# GPIO_AND_SERIAL.net
KiCad netlist of a schematic drawn in Altium Designer
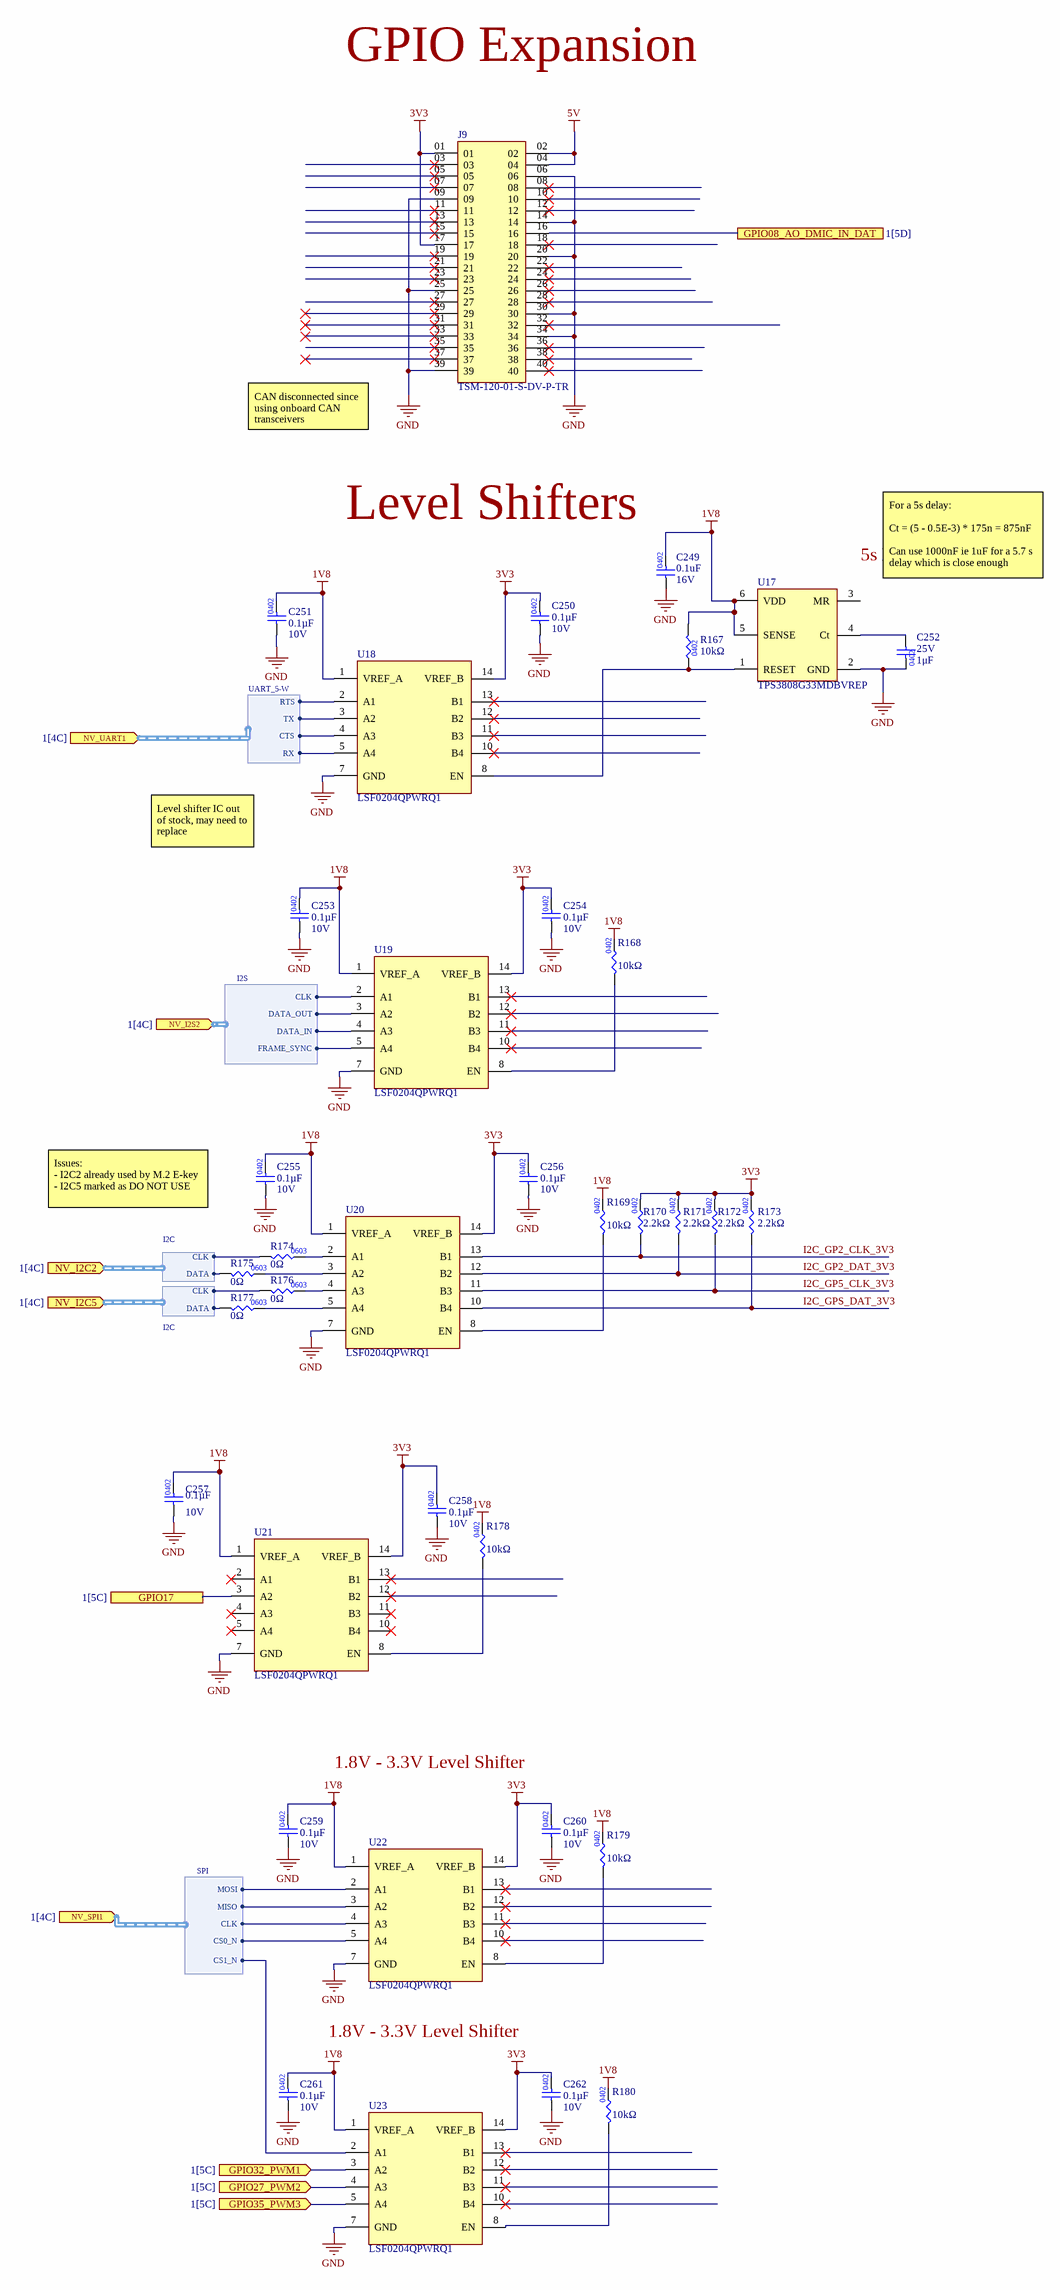
[diagram p0: GPIO AND SERIAL.SchDoc]

(export (version "E")
  (design (tool "Eeschema 10.0.6"))
  (components
    (comp (ref "C249")
      (value "CAP_0.1uF_16V_X7R_0402")
      (footprint "CAP0402")
      (description "CAP CER 0.1UF 16V X7R 0402")
      (fields (field (name "CAPACITANCE") "0.1uF") (field (name "VOLTAGE RATING") "16V"))
      (libsource (lib "UWRT_Schematic_Library_2020") (part "CAP_0.1uF_16V_X7R_0402"))
    )
    (comp (ref "C250")
      (value "0.1µF")
      (footprint "CAP0402")
      (description "CAP CER 0.1UF 10V X7R 0402")
      (fields (field (name "VOLTAGE RATING") "10V") (field (name "Comment") "CAP_0.1uF_10V_0402"))
      (libsource (lib "UWRT_Schematic_Library_2020") (part "CAP_0.1uF_10V_0402"))
    )
    (comp (ref "C251")
      (value "0.1µF")
      (footprint "CAP0402")
      (description "CAP CER 0.1UF 10V X7R 0402")
      (fields (field (name "VOLTAGE RATING") "10V") (field (name "Comment") "CAP_0.1uF_10V_0402"))
      (libsource (lib "UWRT_Schematic_Library_2020") (part "CAP_0.1uF_10V_0402"))
    )
    (comp (ref "C252")
      (value "1μF")
      (footprint "CAP0402")
      (description "CAP CER 1UF 25V X5R 0402")
      (fields (field (name "VOLTAGE") "25V") (field (name "Comment") "CAP_1uF_25V_0402"))
      (libsource (lib "UWRT_Schematic_Library_2020") (part "CAP_1uF_25V_0402"))
    )
    (comp (ref "C253")
      (value "0.1µF")
      (footprint "CAP0402")
      (description "CAP CER 0.1UF 10V X7R 0402")
      (fields (field (name "VOLTAGE RATING") "10V") (field (name "Comment") "CAP_0.1uF_10V_0402"))
      (libsource (lib "UWRT_Schematic_Library_2020") (part "CAP_0.1uF_10V_0402"))
    )
    (comp (ref "C254")
      (value "0.1µF")
      (footprint "CAP0402")
      (description "CAP CER 0.1UF 10V X7R 0402")
      (fields (field (name "VOLTAGE RATING") "10V") (field (name "Comment") "CAP_0.1uF_10V_0402"))
      (libsource (lib "UWRT_Schematic_Library_2020") (part "CAP_0.1uF_10V_0402"))
    )
    (comp (ref "C255")
      (value "0.1µF")
      (footprint "CAP0402")
      (description "CAP CER 0.1UF 10V X7R 0402")
      (fields (field (name "VOLTAGE RATING") "10V") (field (name "Comment") "CAP_0.1uF_10V_0402"))
      (libsource (lib "UWRT_Schematic_Library_2020") (part "CAP_0.1uF_10V_0402"))
    )
    (comp (ref "C256")
      (value "0.1µF")
      (footprint "CAP0402")
      (description "CAP CER 0.1UF 10V X7R 0402")
      (fields (field (name "VOLTAGE RATING") "10V") (field (name "Comment") "CAP_0.1uF_10V_0402"))
      (libsource (lib "UWRT_Schematic_Library_2020") (part "CAP_0.1uF_10V_0402"))
    )
    (comp (ref "C257")
      (value "0.1µF")
      (footprint "CAP0402")
      (description "CAP CER 0.1UF 10V X7R 0402")
      (fields (field (name "VOLTAGE RATING") "10V") (field (name "Comment") "CAP_0.1uF_10V_0402"))
      (libsource (lib "UWRT_Schematic_Library_2020") (part "CAP_0.1uF_10V_0402"))
    )
    (comp (ref "C258")
      (value "0.1µF")
      (footprint "CAP0402")
      (description "CAP CER 0.1UF 10V X7R 0402")
      (fields (field (name "VOLTAGE RATING") "10V") (field (name "Comment") "CAP_0.1uF_10V_0402"))
      (libsource (lib "UWRT_Schematic_Library_2020") (part "CAP_0.1uF_10V_0402"))
    )
    (comp (ref "C259")
      (value "0.1µF")
      (footprint "CAP0402")
      (description "CAP CER 0.1UF 10V X7R 0402")
      (fields (field (name "VOLTAGE RATING") "10V") (field (name "Comment") "CAP_0.1uF_10V_0402"))
      (libsource (lib "UWRT_Schematic_Library_2020") (part "CAP_0.1uF_10V_0402"))
    )
    (comp (ref "C260")
      (value "0.1µF")
      (footprint "CAP0402")
      (description "CAP CER 0.1UF 10V X7R 0402")
      (fields (field (name "VOLTAGE RATING") "10V") (field (name "Comment") "CAP_0.1uF_10V_0402"))
      (libsource (lib "UWRT_Schematic_Library_2020") (part "CAP_0.1uF_10V_0402"))
    )
    (comp (ref "C261")
      (value "0.1µF")
      (footprint "CAP0402")
      (description "CAP CER 0.1UF 10V X7R 0402")
      (fields (field (name "VOLTAGE RATING") "10V") (field (name "Comment") "CAP_0.1uF_10V_0402"))
      (libsource (lib "UWRT_Schematic_Library_2020") (part "CAP_0.1uF_10V_0402"))
    )
    (comp (ref "C262")
      (value "0.1µF")
      (footprint "CAP0402")
      (description "CAP CER 0.1UF 10V X7R 0402")
      (fields (field (name "VOLTAGE RATING") "10V") (field (name "Comment") "CAP_0.1uF_10V_0402"))
      (libsource (lib "UWRT_Schematic_Library_2020") (part "CAP_0.1uF_10V_0402"))
    )
    (comp (ref "J9")
      (value "TSM-120-01-S-DV-P-TR")
      (footprint "SAMTEC_TSM-120-01-S-DV-P-TR")
      (description "CONN HEADER SMD 40POS 2.54MM")
      (fields (field (name "MANUFACTURER PART NUMBER 1") "TSM-120-01-S-DV-P-TR"))
      (libsource (lib "UWRT_Schematic_Library_2020") (part "TSM-120-01-S-DV-P-TR"))
    )
    (comp (ref "R167")
      (value "RES_10kΩ_0402_1%")
      (footprint "RES0402")
      (description "RES 10K OHM 1% 1/16W 0402")
      (fields (field (name "TOLERANCE") "1%") (field (name "RESISTANCE") "10kΩ"))
      (libsource (lib "") (part "RES_10kΩ_0402_1%_1"))
    )
    (comp (ref "R168")
      (value "10kΩ")
      (footprint "RES0402")
      (description "RES SMD 10K OHM 1% 1/16W 0402")
      (fields (field (name "POWER") "0.063W, 1/16W") (field (name "TOLERANCE") "1%"))
      (libsource (lib "UWRT_Schematic_Library_2020") (part "RES_10kΩ_0402_1%"))
    )
    (comp (ref "R169")
      (value "10kΩ")
      (footprint "RES0402")
      (description "RES SMD 10K OHM 1% 1/16W 0402")
      (fields (field (name "POWER") "0.063W, 1/16W") (field (name "TOLERANCE") "1%"))
      (libsource (lib "UWRT_Schematic_Library_2020") (part "RES_10kΩ_0402_1%"))
    )
    (comp (ref "R170")
      (value "2.2kΩ")
      (footprint "RES0402")
      (description "RES SMD 2.2K OHM 5% 1/10W 0402")
      (fields (field (name "Comment") "RES_2.2kΩ_0402_5%"))
      (libsource (lib "UWRT_Schematic_Library_2020") (part "RES_2.2kΩ_0402_5%"))
    )
    (comp (ref "R171")
      (value "2.2kΩ")
      (footprint "RES0402")
      (description "RES SMD 2.2K OHM 5% 1/10W 0402")
      (fields (field (name "Comment") "RES_2.2kΩ_0402_5%"))
      (libsource (lib "UWRT_Schematic_Library_2020") (part "RES_2.2kΩ_0402_5%"))
    )
    (comp (ref "R172")
      (value "2.2kΩ")
      (footprint "RES0402")
      (description "RES SMD 2.2K OHM 5% 1/10W 0402")
      (fields (field (name "Comment") "RES_2.2kΩ_0402_5%"))
      (libsource (lib "UWRT_Schematic_Library_2020") (part "RES_2.2kΩ_0402_5%"))
    )
    (comp (ref "R173")
      (value "2.2kΩ")
      (footprint "RES0402")
      (description "RES SMD 2.2K OHM 5% 1/10W 0402")
      (fields (field (name "Comment") "RES_2.2kΩ_0402_5%"))
      (libsource (lib "UWRT_Schematic_Library_2020") (part "RES_2.2kΩ_0402_5%"))
    )
    (comp (ref "R174")
      (value "0Ω")
      (footprint "RES0603")
      (description "RES 0 OHM JUMPER 1/10W 0603")
      (fields (field (name "Comment") "RES_0Ω_0603"))
      (libsource (lib "UWRT_Schematic_Library_2020") (part "RES_0Ω_0603"))
    )
    (comp (ref "R175")
      (value "0Ω")
      (footprint "RES0603")
      (description "RES 0 OHM JUMPER 1/10W 0603")
      (fields (field (name "Comment") "RES_0Ω_0603"))
      (libsource (lib "UWRT_Schematic_Library_2020") (part "RES_0Ω_0603"))
    )
    (comp (ref "R176")
      (value "0Ω")
      (footprint "RES0603")
      (description "RES 0 OHM JUMPER 1/10W 0603")
      (fields (field (name "Comment") "RES_0Ω_0603"))
      (libsource (lib "UWRT_Schematic_Library_2020") (part "RES_0Ω_0603"))
    )
    (comp (ref "R177")
      (value "0Ω")
      (footprint "RES0603")
      (description "RES 0 OHM JUMPER 1/10W 0603")
      (fields (field (name "Comment") "RES_0Ω_0603"))
      (libsource (lib "UWRT_Schematic_Library_2020") (part "RES_0Ω_0603"))
    )
    (comp (ref "R178")
      (value "10kΩ")
      (footprint "RES0402")
      (description "RES SMD 10K OHM 1% 1/16W 0402")
      (fields (field (name "POWER") "0.063W, 1/16W") (field (name "TOLERANCE") "1%"))
      (libsource (lib "UWRT_Schematic_Library_2020") (part "RES_10kΩ_0402_1%"))
    )
    (comp (ref "R179")
      (value "10kΩ")
      (footprint "RES0402")
      (description "RES SMD 10K OHM 1% 1/16W 0402")
      (fields (field (name "POWER") "0.063W, 1/16W") (field (name "TOLERANCE") "1%"))
      (libsource (lib "UWRT_Schematic_Library_2020") (part "RES_10kΩ_0402_1%"))
    )
    (comp (ref "R180")
      (value "10kΩ")
      (footprint "RES0402")
      (description "RES SMD 10K OHM 1% 1/16W 0402")
      (fields (field (name "POWER") "0.063W, 1/16W") (field (name "TOLERANCE") "1%"))
      (libsource (lib "UWRT_Schematic_Library_2020") (part "RES_10kΩ_0402_1%"))
    )
    (comp (ref "U17")
      (value "TPS3808G33MDBVREP")
      (footprint "TPS3808G33MDBVREP")
      (description "IC SUPERVISOR 1 CHANNEL SOT23-6")
      (fields (field (name "MANUFACTURER PART NUMBER 1") "TPS3808G33MDBVREP"))
      (libsource (lib "UWRT_Schematic_Library_2020") (part "TPS3808G33MDBVREP"))
    )
    (comp (ref "U18")
      (value "LSF0204QPWRQ1")
      (footprint "14-TSSOP")
      (libsource (lib "UWRT_Schematic_Library_2020") (part "LSF0204QPWRQ1"))
    )
    (comp (ref "U19")
      (value "LSF0204QPWRQ1")
      (footprint "14-TSSOP")
      (libsource (lib "UWRT_Schematic_Library_2020") (part "LSF0204QPWRQ1"))
    )
    (comp (ref "U20")
      (value "LSF0204QPWRQ1")
      (footprint "14-TSSOP")
      (libsource (lib "UWRT_Schematic_Library_2020") (part "LSF0204QPWRQ1"))
    )
    (comp (ref "U21")
      (value "LSF0204QPWRQ1")
      (footprint "14-TSSOP")
      (libsource (lib "UWRT_Schematic_Library_2020") (part "LSF0204QPWRQ1"))
    )
    (comp (ref "U22")
      (value "LSF0204QPWRQ1")
      (footprint "14-TSSOP")
      (libsource (lib "UWRT_Schematic_Library_2020") (part "LSF0204QPWRQ1"))
    )
    (comp (ref "U23")
      (value "LSF0204QPWRQ1")
      (footprint "14-TSSOP")
      (libsource (lib "UWRT_Schematic_Library_2020") (part "LSF0204QPWRQ1"))
    )
  )
  (nets
    (net (code "5") (name "/CS0_N") (class "Default")
      (node (ref "U22") (pin "5") (pinfunction "A4_5") (pintype "passive"))
    )
    (net (code "6") (name "/CS1_N") (class "Default")
      (node (ref "U23") (pin "2") (pinfunction "A1_2") (pintype "passive"))
    )
    (net (code "7") (name "/CTS") (class "Default")
      (node (ref "U18") (pin "4") (pinfunction "A3_4") (pintype "passive"))
    )
    (net (code "8") (name "/DATA_IN") (class "Default")
      (node (ref "U19") (pin "4") (pinfunction "A3_4") (pintype "passive"))
    )
    (net (code "9") (name "/DATA_OUT") (class "Default")
      (node (ref "U19") (pin "3") (pinfunction "A2_3") (pintype "passive"))
    )
    (net (code "10") (name "/FRAME_SYNC") (class "Default")
      (node (ref "U19") (pin "5") (pinfunction "A4_5") (pintype "passive"))
    )
    (net (code "11") (name "/GPIO08_AO_DMIC_IN_DAT") (class "Default")
      (node (ref "J9") (pin "16") (pinfunction "16_16") (pintype "passive"))
    )
    (net (code "12") (name "/GPIO17") (class "Default")
      (node (ref "U21") (pin "3") (pinfunction "A2_3") (pintype "passive"))
    )
    (net (code "13") (name "/GPIO27_PWM2") (class "Default")
      (node (ref "U23") (pin "4") (pinfunction "A3_4") (pintype "passive"))
    )
    (net (code "14") (name "/GPIO32_PWM1") (class "Default")
      (node (ref "U23") (pin "3") (pinfunction "A2_3") (pintype "passive"))
    )
    (net (code "15") (name "/GPIO35_PWM3") (class "Default")
      (node (ref "U23") (pin "5") (pinfunction "A4_5") (pintype "passive"))
    )
    (net (code "16") (name "/I2C_GP2_CLK_3V3") (class "Default")
      (node (ref "R170") (pin "1") (pinfunction "1_1") (pintype "passive"))
      (node (ref "U20") (pin "13") (pinfunction "B1_13") (pintype "passive"))
    )
    (net (code "17") (name "/I2C_GP2_DAT_3V3") (class "Default")
      (node (ref "R171") (pin "1") (pinfunction "1_1") (pintype "passive"))
      (node (ref "U20") (pin "12") (pinfunction "B2_12") (pintype "passive"))
    )
    (net (code "18") (name "/I2C_GP5_CLK_3V3") (class "Default")
      (node (ref "R172") (pin "1") (pinfunction "1_1") (pintype "passive"))
      (node (ref "U20") (pin "11") (pinfunction "B3_11") (pintype "passive"))
    )
    (net (code "19") (name "/I2C_GPS_DAT_3V3") (class "Default")
      (node (ref "R173") (pin "1") (pinfunction "1_1") (pintype "passive"))
      (node (ref "U20") (pin "10") (pinfunction "B4_10") (pintype "passive"))
    )
    (net (code "20") (name "/MISO") (class "Default")
      (node (ref "U22") (pin "3") (pinfunction "A2_3") (pintype "passive"))
    )
    (net (code "21") (name "/MOSI") (class "Default")
      (node (ref "U22") (pin "2") (pinfunction "A1_2") (pintype "passive"))
    )
    (net (code "22") (name "/RTS") (class "Default")
      (node (ref "U18") (pin "2") (pinfunction "A1_2") (pintype "passive"))
    )
    (net (code "23") (name "/RX") (class "Default")
      (node (ref "U18") (pin "5") (pinfunction "A4_5") (pintype "passive"))
    )
    (net (code "24") (name "/TX") (class "Default")
      (node (ref "U18") (pin "3") (pinfunction "A2_3") (pintype "passive"))
    )
    (net (code "29") (name "1V8") (class "Default")
      (node (ref "C249") (pin "2") (pinfunction "2_2") (pintype "passive"))
      (node (ref "C251") (pin "2") (pinfunction "2_2") (pintype "passive"))
      (node (ref "C253") (pin "2") (pinfunction "2_2") (pintype "passive"))
      (node (ref "C255") (pin "2") (pinfunction "2_2") (pintype "passive"))
      (node (ref "C257") (pin "2") (pinfunction "2_2") (pintype "passive"))
      (node (ref "C259") (pin "2") (pinfunction "2_2") (pintype "passive"))
      (node (ref "C261") (pin "2") (pinfunction "2_2") (pintype "passive"))
      (node (ref "R167") (pin "2") (pinfunction "2_2") (pintype "passive"))
      (node (ref "R168") (pin "2") (pinfunction "2_2") (pintype "passive"))
      (node (ref "R169") (pin "2") (pinfunction "2_2") (pintype "passive"))
      (node (ref "R178") (pin "2") (pinfunction "2_2") (pintype "passive"))
      (node (ref "R179") (pin "2") (pinfunction "2_2") (pintype "passive"))
      (node (ref "R180") (pin "2") (pinfunction "2_2") (pintype "passive"))
      (node (ref "U17") (pin "5") (pinfunction "SENSE_5") (pintype "passive"))
      (node (ref "U17") (pin "6") (pinfunction "VDD_6") (pintype "passive"))
      (node (ref "U18") (pin "1") (pinfunction "VREF_A_1") (pintype "passive"))
      (node (ref "U19") (pin "1") (pinfunction "VREF_A_1") (pintype "passive"))
      (node (ref "U20") (pin "1") (pinfunction "VREF_A_1") (pintype "passive"))
      (node (ref "U21") (pin "1") (pinfunction "VREF_A_1") (pintype "passive"))
      (node (ref "U22") (pin "1") (pinfunction "VREF_A_1") (pintype "passive"))
      (node (ref "U23") (pin "1") (pinfunction "VREF_A_1") (pintype "passive"))
    )
    (net (code "30") (name "3V3") (class "Default")
      (node (ref "C250") (pin "2") (pinfunction "2_2") (pintype "passive"))
      (node (ref "C254") (pin "2") (pinfunction "2_2") (pintype "passive"))
      (node (ref "C256") (pin "2") (pinfunction "2_2") (pintype "passive"))
      (node (ref "C258") (pin "2") (pinfunction "2_2") (pintype "passive"))
      (node (ref "C260") (pin "2") (pinfunction "2_2") (pintype "passive"))
      (node (ref "C262") (pin "2") (pinfunction "2_2") (pintype "passive"))
      (node (ref "J9") (pin "01") (pinfunction "01_01") (pintype "passive"))
      (node (ref "J9") (pin "17") (pinfunction "17_17") (pintype "passive"))
      (node (ref "R170") (pin "2") (pinfunction "2_2") (pintype "passive"))
      (node (ref "R171") (pin "2") (pinfunction "2_2") (pintype "passive"))
      (node (ref "R172") (pin "2") (pinfunction "2_2") (pintype "passive"))
      (node (ref "R173") (pin "2") (pinfunction "2_2") (pintype "passive"))
      (node (ref "U18") (pin "14") (pinfunction "VREF_B_14") (pintype "passive"))
      (node (ref "U19") (pin "14") (pinfunction "VREF_B_14") (pintype "passive"))
      (node (ref "U20") (pin "14") (pinfunction "VREF_B_14") (pintype "passive"))
      (node (ref "U21") (pin "14") (pinfunction "VREF_B_14") (pintype "passive"))
      (node (ref "U22") (pin "14") (pinfunction "VREF_B_14") (pintype "passive"))
      (node (ref "U23") (pin "14") (pinfunction "VREF_B_14") (pintype "passive"))
    )
    (net (code "31") (name "5V") (class "Default")
      (node (ref "J9") (pin "02") (pinfunction "02_02") (pintype "passive"))
      (node (ref "J9") (pin "04") (pinfunction "04_04") (pintype "passive"))
    )
    (net (code "32") (name "GND") (class "Default")
      (node (ref "C249") (pin "1") (pinfunction "1_1") (pintype "passive"))
      (node (ref "C250") (pin "1") (pinfunction "1_1") (pintype "passive"))
      (node (ref "C251") (pin "1") (pinfunction "1_1") (pintype "passive"))
      (node (ref "C252") (pin "1") (pinfunction "1_1") (pintype "passive"))
      (node (ref "C253") (pin "1") (pinfunction "1_1") (pintype "passive"))
      (node (ref "C254") (pin "1") (pinfunction "1_1") (pintype "passive"))
      (node (ref "C255") (pin "1") (pinfunction "1_1") (pintype "passive"))
      (node (ref "C256") (pin "1") (pinfunction "1_1") (pintype "passive"))
      (node (ref "C257") (pin "1") (pinfunction "1_1") (pintype "passive"))
      (node (ref "C258") (pin "1") (pinfunction "1_1") (pintype "passive"))
      (node (ref "C259") (pin "1") (pinfunction "1_1") (pintype "passive"))
      (node (ref "C260") (pin "1") (pinfunction "1_1") (pintype "passive"))
      (node (ref "C261") (pin "1") (pinfunction "1_1") (pintype "passive"))
      (node (ref "C262") (pin "1") (pinfunction "1_1") (pintype "passive"))
      (node (ref "J9") (pin "06") (pinfunction "06_06") (pintype "passive"))
      (node (ref "J9") (pin "09") (pinfunction "09_09") (pintype "passive"))
      (node (ref "J9") (pin "14") (pinfunction "14_14") (pintype "passive"))
      (node (ref "J9") (pin "20") (pinfunction "20_20") (pintype "passive"))
      (node (ref "J9") (pin "25") (pinfunction "25_25") (pintype "passive"))
      (node (ref "J9") (pin "30") (pinfunction "30_30") (pintype "passive"))
      (node (ref "J9") (pin "34") (pinfunction "34_34") (pintype "passive"))
      (node (ref "J9") (pin "39") (pinfunction "39_39") (pintype "passive"))
      (node (ref "U17") (pin "2") (pinfunction "GND_2") (pintype "passive"))
      (node (ref "U18") (pin "7") (pinfunction "GND_7") (pintype "passive"))
      (node (ref "U19") (pin "7") (pinfunction "GND_7") (pintype "passive"))
      (node (ref "U20") (pin "7") (pinfunction "GND_7") (pintype "passive"))
      (node (ref "U21") (pin "7") (pinfunction "GND_7") (pintype "passive"))
      (node (ref "U22") (pin "7") (pinfunction "GND_7") (pintype "passive"))
      (node (ref "U23") (pin "7") (pinfunction "GND_7") (pintype "passive"))
    )
    (net (code "33") (name "Net-(U17-Ct)") (class "Default")
      (node (ref "C252") (pin "2") (pinfunction "2_2") (pintype "passive"))
      (node (ref "U17") (pin "4") (pinfunction "Ct_4") (pintype "passive"))
    )
    (net (code "34") (name "Net-(U17-RESET)") (class "Default")
      (node (ref "R167") (pin "1") (pinfunction "1_1") (pintype "passive"))
      (node (ref "U17") (pin "1") (pinfunction "RESET_1") (pintype "passive"))
      (node (ref "U18") (pin "8") (pinfunction "EN_8") (pintype "passive"))
    )
    (net (code "35") (name "Net-(U19-EN)") (class "Default")
      (node (ref "R168") (pin "1") (pinfunction "1_1") (pintype "passive"))
      (node (ref "U19") (pin "8") (pinfunction "EN_8") (pintype "passive"))
    )
    (net (code "36") (name "Net-(U20-A1)") (class "Default")
      (node (ref "R174") (pin "2") (pinfunction "2_2") (pintype "passive"))
      (node (ref "U20") (pin "2") (pinfunction "A1_2") (pintype "passive"))
    )
    (net (code "37") (name "Net-(U20-A2)") (class "Default")
      (node (ref "R175") (pin "2") (pinfunction "2_2") (pintype "passive"))
      (node (ref "U20") (pin "3") (pinfunction "A2_3") (pintype "passive"))
    )
    (net (code "38") (name "Net-(U20-A3)") (class "Default")
      (node (ref "R176") (pin "2") (pinfunction "2_2") (pintype "passive"))
      (node (ref "U20") (pin "4") (pinfunction "A3_4") (pintype "passive"))
    )
    (net (code "39") (name "Net-(U20-A4)") (class "Default")
      (node (ref "R177") (pin "2") (pinfunction "2_2") (pintype "passive"))
      (node (ref "U20") (pin "5") (pinfunction "A4_5") (pintype "passive"))
    )
    (net (code "40") (name "Net-(U20-EN)") (class "Default")
      (node (ref "R169") (pin "1") (pinfunction "1_1") (pintype "passive"))
      (node (ref "U20") (pin "8") (pinfunction "EN_8") (pintype "passive"))
    )
    (net (code "41") (name "Net-(U21-EN)") (class "Default")
      (node (ref "R178") (pin "1") (pinfunction "1_1") (pintype "passive"))
      (node (ref "U21") (pin "8") (pinfunction "EN_8") (pintype "passive"))
    )
    (net (code "42") (name "Net-(U22-EN)") (class "Default")
      (node (ref "R179") (pin "1") (pinfunction "1_1") (pintype "passive"))
      (node (ref "U22") (pin "8") (pinfunction "EN_8") (pintype "passive"))
    )
    (net (code "43") (name "Net-(U23-EN)") (class "Default")
      (node (ref "R180") (pin "1") (pinfunction "1_1") (pintype "passive"))
      (node (ref "U23") (pin "8") (pinfunction "EN_8") (pintype "passive"))
    )
    (net (code "44") (name "unconnected-(J9-Pad03)") (class "Default")
      (node (ref "J9") (pin "03") (pinfunction "03_03") (pintype "passive+no_connect"))
    )
    (net (code "45") (name "unconnected-(J9-Pad05)") (class "Default")
      (node (ref "J9") (pin "05") (pinfunction "05_05") (pintype "passive+no_connect"))
    )
    (net (code "46") (name "unconnected-(J9-Pad07)") (class "Default")
      (node (ref "J9") (pin "07") (pinfunction "07_07") (pintype "passive+no_connect"))
    )
    (net (code "47") (name "unconnected-(J9-Pad08)") (class "Default")
      (node (ref "J9") (pin "08") (pinfunction "08_08") (pintype "passive+no_connect"))
    )
    (net (code "48") (name "unconnected-(J9-Pad10)") (class "Default")
      (node (ref "J9") (pin "10") (pinfunction "10_10") (pintype "passive+no_connect"))
    )
    (net (code "49") (name "unconnected-(J9-Pad11)") (class "Default")
      (node (ref "J9") (pin "11") (pinfunction "11_11") (pintype "passive+no_connect"))
    )
    (net (code "50") (name "unconnected-(J9-Pad12)") (class "Default")
      (node (ref "J9") (pin "12") (pinfunction "12_12") (pintype "passive+no_connect"))
    )
    (net (code "51") (name "unconnected-(J9-Pad13)") (class "Default")
      (node (ref "J9") (pin "13") (pinfunction "13_13") (pintype "passive+no_connect"))
    )
    (net (code "52") (name "unconnected-(J9-Pad15)") (class "Default")
      (node (ref "J9") (pin "15") (pinfunction "15_15") (pintype "passive+no_connect"))
    )
    (net (code "53") (name "unconnected-(J9-Pad18)") (class "Default")
      (node (ref "J9") (pin "18") (pinfunction "18_18") (pintype "passive+no_connect"))
    )
    (net (code "54") (name "unconnected-(J9-Pad19)") (class "Default")
      (node (ref "J9") (pin "19") (pinfunction "19_19") (pintype "passive+no_connect"))
    )
    (net (code "55") (name "unconnected-(J9-Pad21)") (class "Default")
      (node (ref "J9") (pin "21") (pinfunction "21_21") (pintype "passive+no_connect"))
    )
    (net (code "56") (name "unconnected-(J9-Pad22)") (class "Default")
      (node (ref "J9") (pin "22") (pinfunction "22_22") (pintype "passive+no_connect"))
    )
    (net (code "57") (name "unconnected-(J9-Pad23)") (class "Default")
      (node (ref "J9") (pin "23") (pinfunction "23_23") (pintype "passive+no_connect"))
    )
    (net (code "58") (name "unconnected-(J9-Pad24)") (class "Default")
      (node (ref "J9") (pin "24") (pinfunction "24_24") (pintype "passive+no_connect"))
    )
    (net (code "59") (name "unconnected-(J9-Pad26)") (class "Default")
      (node (ref "J9") (pin "26") (pinfunction "26_26") (pintype "passive+no_connect"))
    )
    (net (code "60") (name "unconnected-(J9-Pad27)") (class "Default")
      (node (ref "J9") (pin "27") (pinfunction "27_27") (pintype "passive+no_connect"))
    )
    (net (code "61") (name "unconnected-(J9-Pad28)") (class "Default")
      (node (ref "J9") (pin "28") (pinfunction "28_28") (pintype "passive+no_connect"))
    )
    (net (code "62") (name "unconnected-(J9-Pad29)") (class "Default")
      (node (ref "J9") (pin "29") (pinfunction "29_29") (pintype "passive+no_connect"))
    )
    (net (code "63") (name "unconnected-(J9-Pad31)") (class "Default")
      (node (ref "J9") (pin "31") (pinfunction "31_31") (pintype "passive+no_connect"))
    )
    (net (code "64") (name "unconnected-(J9-Pad32)") (class "Default")
      (node (ref "J9") (pin "32") (pinfunction "32_32") (pintype "passive+no_connect"))
    )
    (net (code "65") (name "unconnected-(J9-Pad33)") (class "Default")
      (node (ref "J9") (pin "33") (pinfunction "33_33") (pintype "passive+no_connect"))
    )
    (net (code "66") (name "unconnected-(J9-Pad35)") (class "Default")
      (node (ref "J9") (pin "35") (pinfunction "35_35") (pintype "passive+no_connect"))
    )
    (net (code "67") (name "unconnected-(J9-Pad36)") (class "Default")
      (node (ref "J9") (pin "36") (pinfunction "36_36") (pintype "passive+no_connect"))
    )
    (net (code "68") (name "unconnected-(J9-Pad37)") (class "Default")
      (node (ref "J9") (pin "37") (pinfunction "37_37") (pintype "passive+no_connect"))
    )
    (net (code "69") (name "unconnected-(J9-Pad38)") (class "Default")
      (node (ref "J9") (pin "38") (pinfunction "38_38") (pintype "passive+no_connect"))
    )
    (net (code "70") (name "unconnected-(J9-Pad40)") (class "Default")
      (node (ref "J9") (pin "40") (pinfunction "40_40") (pintype "passive+no_connect"))
    )
    (net (code "71") (name "unconnected-(R174-Pad1)") (class "Default")
      (node (ref "R174") (pin "1") (pinfunction "1_1") (pintype "passive"))
    )
    (net (code "72") (name "unconnected-(R175-Pad1)") (class "Default")
      (node (ref "R175") (pin "1") (pinfunction "1_1") (pintype "passive"))
    )
    (net (code "73") (name "unconnected-(R176-Pad1)") (class "Default")
      (node (ref "R176") (pin "1") (pinfunction "1_1") (pintype "passive"))
    )
    (net (code "74") (name "unconnected-(R177-Pad1)") (class "Default")
      (node (ref "R177") (pin "1") (pinfunction "1_1") (pintype "passive"))
    )
    (net (code "75") (name "unconnected-(U17-MR-Pad3)") (class "Default")
      (node (ref "U17") (pin "3") (pinfunction "MR_3") (pintype "passive"))
    )
    (net (code "76") (name "unconnected-(U18-B1-Pad13)") (class "Default")
      (node (ref "U18") (pin "13") (pinfunction "B1_13") (pintype "passive+no_connect"))
    )
    (net (code "77") (name "unconnected-(U18-B2-Pad12)") (class "Default")
      (node (ref "U18") (pin "12") (pinfunction "B2_12") (pintype "passive+no_connect"))
    )
    (net (code "78") (name "unconnected-(U18-B3-Pad11)") (class "Default")
      (node (ref "U18") (pin "11") (pinfunction "B3_11") (pintype "passive+no_connect"))
    )
    (net (code "79") (name "unconnected-(U18-B4-Pad10)") (class "Default")
      (node (ref "U18") (pin "10") (pinfunction "B4_10") (pintype "passive+no_connect"))
    )
    (net (code "80") (name "unconnected-(U19-A1-Pad2)") (class "Default")
      (node (ref "U19") (pin "2") (pinfunction "A1_2") (pintype "passive"))
    )
    (net (code "81") (name "unconnected-(U19-B1-Pad13)") (class "Default")
      (node (ref "U19") (pin "13") (pinfunction "B1_13") (pintype "passive+no_connect"))
    )
    (net (code "82") (name "unconnected-(U19-B2-Pad12)") (class "Default")
      (node (ref "U19") (pin "12") (pinfunction "B2_12") (pintype "passive+no_connect"))
    )
    (net (code "83") (name "unconnected-(U19-B3-Pad11)") (class "Default")
      (node (ref "U19") (pin "11") (pinfunction "B3_11") (pintype "passive+no_connect"))
    )
    (net (code "84") (name "unconnected-(U19-B4-Pad10)") (class "Default")
      (node (ref "U19") (pin "10") (pinfunction "B4_10") (pintype "passive+no_connect"))
    )
    (net (code "85") (name "unconnected-(U21-A1-Pad2)") (class "Default")
      (node (ref "U21") (pin "2") (pinfunction "A1_2") (pintype "passive+no_connect"))
    )
    (net (code "86") (name "unconnected-(U21-A3-Pad4)") (class "Default")
      (node (ref "U21") (pin "4") (pinfunction "A3_4") (pintype "passive+no_connect"))
    )
    (net (code "87") (name "unconnected-(U21-A4-Pad5)") (class "Default")
      (node (ref "U21") (pin "5") (pinfunction "A4_5") (pintype "passive+no_connect"))
    )
    (net (code "88") (name "unconnected-(U21-B1-Pad13)") (class "Default")
      (node (ref "U21") (pin "13") (pinfunction "B1_13") (pintype "passive+no_connect"))
    )
    (net (code "89") (name "unconnected-(U21-B2-Pad12)") (class "Default")
      (node (ref "U21") (pin "12") (pinfunction "B2_12") (pintype "passive+no_connect"))
    )
    (net (code "90") (name "unconnected-(U21-B3-Pad11)") (class "Default")
      (node (ref "U21") (pin "11") (pinfunction "B3_11") (pintype "passive+no_connect"))
    )
    (net (code "91") (name "unconnected-(U21-B4-Pad10)") (class "Default")
      (node (ref "U21") (pin "10") (pinfunction "B4_10") (pintype "passive+no_connect"))
    )
    (net (code "92") (name "unconnected-(U22-A3-Pad4)") (class "Default")
      (node (ref "U22") (pin "4") (pinfunction "A3_4") (pintype "passive"))
    )
    (net (code "93") (name "unconnected-(U22-B1-Pad13)") (class "Default")
      (node (ref "U22") (pin "13") (pinfunction "B1_13") (pintype "passive+no_connect"))
    )
    (net (code "94") (name "unconnected-(U22-B2-Pad12)") (class "Default")
      (node (ref "U22") (pin "12") (pinfunction "B2_12") (pintype "passive+no_connect"))
    )
    (net (code "95") (name "unconnected-(U22-B3-Pad11)") (class "Default")
      (node (ref "U22") (pin "11") (pinfunction "B3_11") (pintype "passive+no_connect"))
    )
    (net (code "96") (name "unconnected-(U22-B4-Pad10)") (class "Default")
      (node (ref "U22") (pin "10") (pinfunction "B4_10") (pintype "passive+no_connect"))
    )
    (net (code "97") (name "unconnected-(U23-B1-Pad13)") (class "Default")
      (node (ref "U23") (pin "13") (pinfunction "B1_13") (pintype "passive+no_connect"))
    )
    (net (code "98") (name "unconnected-(U23-B2-Pad12)") (class "Default")
      (node (ref "U23") (pin "12") (pinfunction "B2_12") (pintype "passive+no_connect"))
    )
    (net (code "99") (name "unconnected-(U23-B3-Pad11)") (class "Default")
      (node (ref "U23") (pin "11") (pinfunction "B3_11") (pintype "passive+no_connect"))
    )
    (net (code "100") (name "unconnected-(U23-B4-Pad10)") (class "Default")
      (node (ref "U23") (pin "10") (pinfunction "B4_10") (pintype "passive+no_connect"))
    )
  )
)
